# Rectifier_shutdown_Gate.net
KiCad netlist of a schematic drawn in Altium Designer
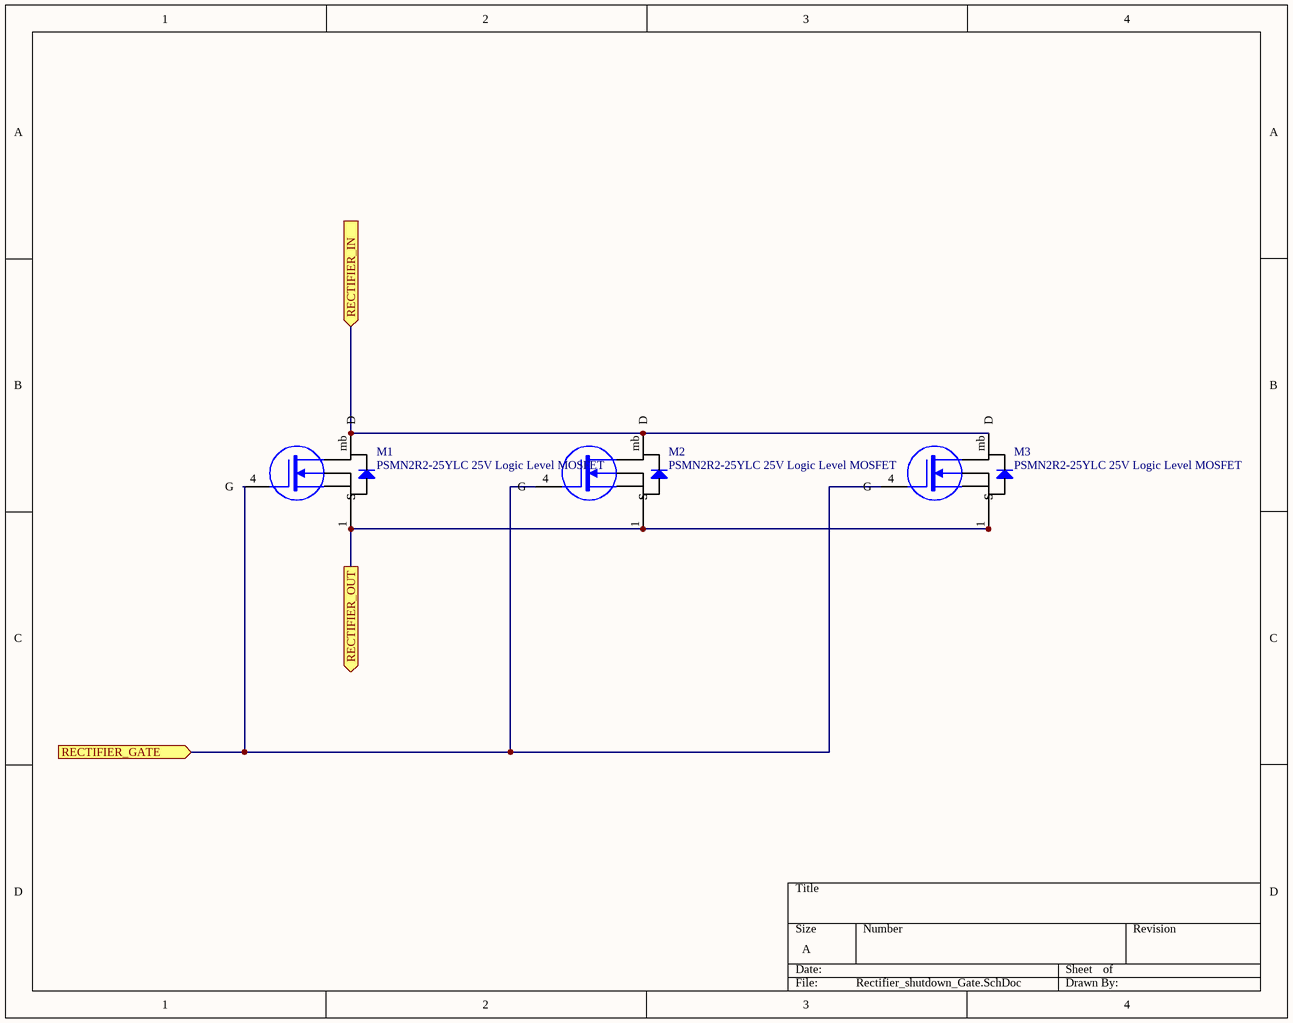
[diagram p0: Rectifier_shutdown_Gate.SchDoc]

(export (version "E")
  (design (tool "Eeschema 10.0.6"))
  (components
    (comp (ref "M1")
      (value "PSMN2R2-25YLC 25V Logic Level MOSFET")
      (footprint "LFPAK-SO8")
      (description "N-Channel 25V 100A (Tc) 106W (Tc) Surface Mount LFPAK56, Power-SO8")
      (fields (field (name "MFRPARTNO") "PSMN2R2-25YLC,115") (field (name "CREATED_BY") "Nick"))
      (libsource (lib "Altium-Lib") (part "PSMN2R2-25YLC 25V Logic Level MOSFET"))
    )
    (comp (ref "M2")
      (value "PSMN2R2-25YLC 25V Logic Level MOSFET")
      (footprint "LFPAK-SO8")
      (description "N-Channel 25V 100A (Tc) 106W (Tc) Surface Mount LFPAK56, Power-SO8")
      (fields (field (name "MFRPARTNO") "PSMN2R2-25YLC,115") (field (name "CREATED_BY") "Nick"))
      (libsource (lib "Altium-Lib") (part "PSMN2R2-25YLC 25V Logic Level MOSFET"))
    )
    (comp (ref "M3")
      (value "PSMN2R2-25YLC 25V Logic Level MOSFET")
      (footprint "LFPAK-SO8")
      (description "N-Channel 25V 100A (Tc) 106W (Tc) Surface Mount LFPAK56, Power-SO8")
      (fields (field (name "MFRPARTNO") "PSMN2R2-25YLC,115") (field (name "CREATED_BY") "Nick"))
      (libsource (lib "Altium-Lib") (part "PSMN2R2-25YLC 25V Logic Level MOSFET"))
    )
  )
  (nets
    (net (code "1") (name "/RECTIFIER_GATE") (class "Default")
      (node (ref "M1") (pin "4") (pinfunction "G_4") (pintype "passive"))
      (node (ref "M2") (pin "4") (pinfunction "G_4") (pintype "passive"))
      (node (ref "M3") (pin "4") (pinfunction "G_4") (pintype "passive"))
    )
    (net (code "2") (name "/RECTIFIER_IN") (class "Default")
      (node (ref "M1") (pin "mb") (pinfunction "D_mb") (pintype "passive"))
      (node (ref "M2") (pin "mb") (pinfunction "D_mb") (pintype "passive"))
      (node (ref "M3") (pin "mb") (pinfunction "D_mb") (pintype "passive"))
    )
    (net (code "3") (name "/RECTIFIER_OUT") (class "Default")
      (node (ref "M1") (pin "1") (pinfunction "S_1") (pintype "passive"))
      (node (ref "M1") (pin "2") (pinfunction "S_2") (pintype "passive"))
      (node (ref "M1") (pin "3") (pinfunction "S_3") (pintype "passive"))
      (node (ref "M2") (pin "1") (pinfunction "S_1") (pintype "passive"))
      (node (ref "M2") (pin "2") (pinfunction "S_2") (pintype "passive"))
      (node (ref "M2") (pin "3") (pinfunction "S_3") (pintype "passive"))
      (node (ref "M3") (pin "1") (pinfunction "S_1") (pintype "passive"))
      (node (ref "M3") (pin "2") (pinfunction "S_2") (pintype "passive"))
      (node (ref "M3") (pin "3") (pinfunction "S_3") (pintype "passive"))
    )
  )
)
